# Pololu_Magnetic_Encoder_Floating_AS5050.net
KiCad netlist of a schematic drawn in EAGLE
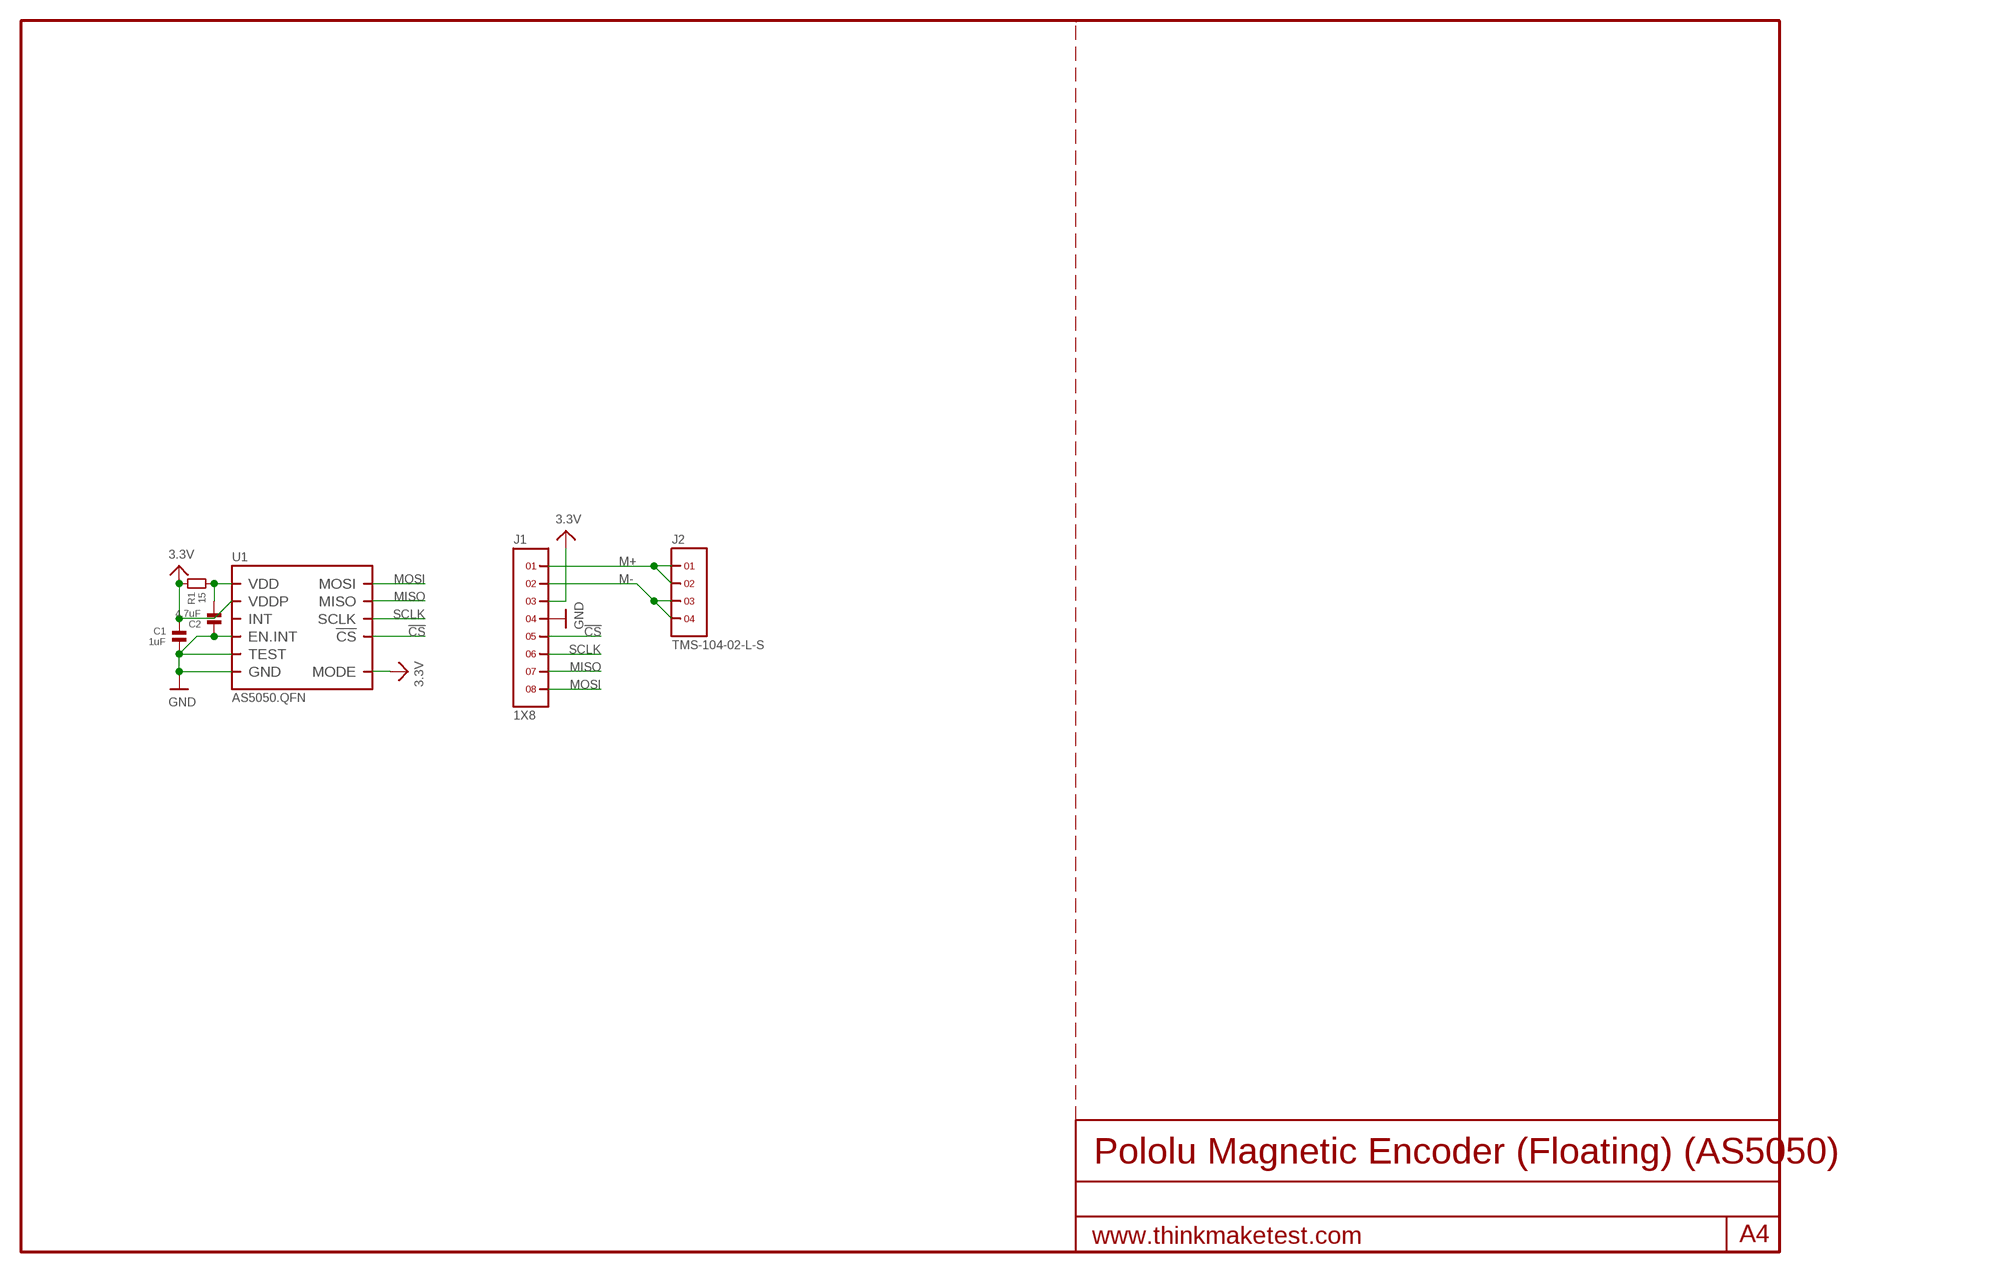
[diagram p0: schematic, sheet 1]

(export (version "E")
  (design (tool "Eeschema 10.0.6"))
  (components
    (comp (ref "C1")
      (value "1uF")
      (footprint "eagle-import:0603")
      (libsource (lib "eagle-import") (part "CAPACITOR.0603"))
    )
    (comp (ref "C2")
      (value "4.7uF")
      (footprint "eagle-import:0603")
      (libsource (lib "eagle-import") (part "CAPACITOR.0603"))
    )
    (comp (ref "J1")
      (value "1X8")
      (footprint "eagle-import:1X8")
      (libsource (lib "eagle-import") (part "1X8"))
    )
    (comp (ref "J2")
      (value "TMS-104-02-L-S")
      (footprint "eagle-import:1X4.LOCK")
      (libsource (lib "eagle-import") (part "1X4.LOCK"))
    )
    (comp (ref "R1")
      (value "15")
      (footprint "eagle-import:0603")
      (libsource (lib "eagle-import") (part "RESISTOR.0603"))
    )
    (comp (ref "U1")
      (value "AS5050.QFN")
      (footprint "eagle-import:QFN.16")
      (libsource (lib "eagle-import") (part "AS5050.QFN"))
    )
  )
  (nets
    (net (code "1") (name "/M+") (class "Default")
      (node (ref "J1") (pin "1") (pinfunction "1_1") (pintype "bidirectional"))
      (node (ref "J2") (pin "1") (pinfunction "1_1") (pintype "bidirectional"))
      (node (ref "J2") (pin "2") (pinfunction "2_2") (pintype "bidirectional"))
    )
    (net (code "2") (name "/M-") (class "Default")
      (node (ref "J1") (pin "2") (pinfunction "2_2") (pintype "bidirectional"))
      (node (ref "J2") (pin "3") (pinfunction "3_3") (pintype "bidirectional"))
      (node (ref "J2") (pin "4") (pinfunction "4_4") (pintype "bidirectional"))
    )
    (net (code "3") (name "/MISO") (class "Default")
      (node (ref "J1") (pin "7") (pinfunction "7_7") (pintype "bidirectional"))
      (node (ref "U1") (pin "2") (pinfunction "MISO_2") (pintype "bidirectional"))
    )
    (net (code "4") (name "/MOSI") (class "Default")
      (node (ref "J1") (pin "8") (pinfunction "8_8") (pintype "bidirectional"))
      (node (ref "U1") (pin "1") (pinfunction "MOSI_1") (pintype "bidirectional"))
    )
    (net (code "5") (name "/SCLK") (class "Default")
      (node (ref "J1") (pin "6") (pinfunction "6_6") (pintype "bidirectional"))
      (node (ref "U1") (pin "3") (pinfunction "SCLK_3") (pintype "bidirectional"))
    )
    (net (code "6") (name "/~{CS}") (class "Default")
      (node (ref "J1") (pin "5") (pinfunction "5_5") (pintype "bidirectional"))
      (node (ref "U1") (pin "4") (pinfunction "~{CS}_4") (pintype "bidirectional"))
    )
    (net (code "7") (name "3.3V") (class "Default")
      (node (ref "C1") (pin "1") (pinfunction "1_1") (pintype "bidirectional"))
      (node (ref "J1") (pin "3") (pinfunction "3_3") (pintype "bidirectional"))
      (node (ref "R1") (pin "1") (pinfunction "1_1") (pintype "bidirectional"))
      (node (ref "U1") (pin "11") (pinfunction "VDDP_11") (pintype "bidirectional"))
      (node (ref "U1") (pin "14") (pinfunction "MODE_14") (pintype "bidirectional"))
    )
    (net (code "8") (name "GND") (class "Default")
      (node (ref "C1") (pin "2") (pinfunction "2_2") (pintype "bidirectional"))
      (node (ref "C2") (pin "1") (pinfunction "1_1") (pintype "bidirectional"))
      (node (ref "J1") (pin "4") (pinfunction "4_4") (pintype "bidirectional"))
      (node (ref "U1") (pin "10") (pinfunction "EN.INT_10") (pintype "bidirectional"))
      (node (ref "U1") (pin "13") (pinfunction "GND_13") (pintype "bidirectional"))
      (node (ref "U1") (pin "9") (pinfunction "TEST_9") (pintype "bidirectional"))
    )
    (net (code "9") (name "Net-(U1-VDD)") (class "Default")
      (node (ref "C2") (pin "2") (pinfunction "2_2") (pintype "bidirectional"))
      (node (ref "R1") (pin "2") (pinfunction "2_2") (pintype "bidirectional"))
      (node (ref "U1") (pin "12") (pinfunction "VDD_12") (pintype "bidirectional"))
    )
    (net (code "10") (name "unconnected-(U1-INT-Pad15)") (class "Default")
      (node (ref "U1") (pin "15") (pinfunction "INT_15") (pintype "bidirectional"))
    )
  )
)
